# RadioRX.net
KiCad netlist of a schematic drawn in EAGLE
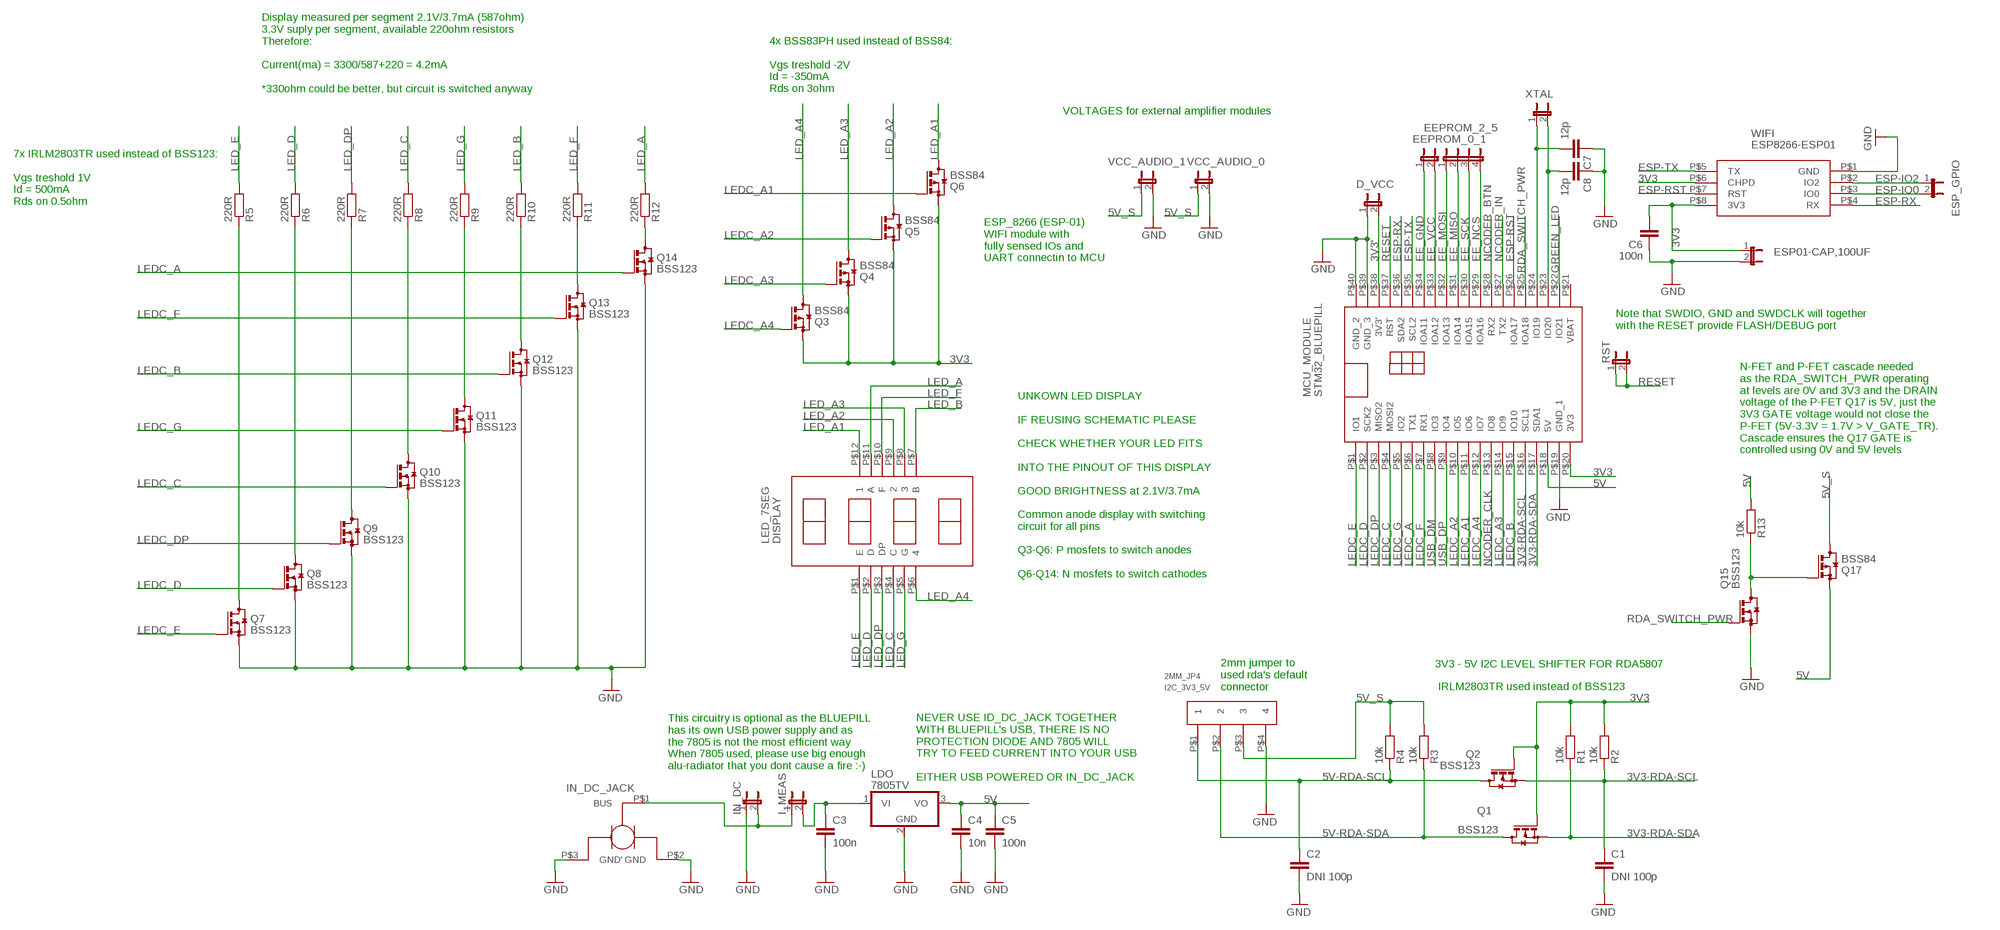
[diagram p0: schematic, sheet 1]

(export (version "E")
  (design (tool "Eeschema 10.0.6"))
  (components
    (comp (ref "C1")
      (value "DNI 100p")
      (footprint "eagle-import:C0805")
      (libsource (lib "eagle-import") (part "C-EUC0805"))
    )
    (comp (ref "C2")
      (value "DNI 100p")
      (footprint "eagle-import:C0805")
      (libsource (lib "eagle-import") (part "C-EUC0805"))
    )
    (comp (ref "C3")
      (value "100n")
      (footprint "eagle-import:C0805")
      (libsource (lib "eagle-import") (part "C-EUC0805"))
    )
    (comp (ref "C4")
      (value "10n")
      (footprint "eagle-import:C0805")
      (libsource (lib "eagle-import") (part "C-EUC0805"))
    )
    (comp (ref "C5")
      (value "100n")
      (footprint "eagle-import:C0805")
      (libsource (lib "eagle-import") (part "C-EUC0805"))
    )
    (comp (ref "C6")
      (value "100n")
      (footprint "eagle-import:C0805")
      (libsource (lib "eagle-import") (part "C-EUC0805"))
    )
    (comp (ref "C7")
      (value "12p")
      (footprint "eagle-import:C0603")
      (libsource (lib "eagle-import") (part "C-EUC0603"))
    )
    (comp (ref "C8")
      (value "12p")
      (footprint "eagle-import:C0603")
      (libsource (lib "eagle-import") (part "C-EUC0603"))
    )
    (comp (ref "DISPLAY")
      (value "LED_7SEG")
      (footprint "eagle-import:LED_7SEG")
      (libsource (lib "eagle-import") (part "LED_7SEG"))
    )
    (comp (ref "D_VCC")
      (value "JP1E")
      (footprint "eagle-import:JP1")
      (libsource (lib "eagle-import") (part "JP1E"))
    )
    (comp (ref "EEPROM_0_1")
      (value "JP1E")
      (footprint "eagle-import:JP1")
      (libsource (lib "eagle-import") (part "JP1E"))
    )
    (comp (ref "EEPROM_2_5")
      (value "JP4E")
      (footprint "eagle-import:JP4")
      (libsource (lib "eagle-import") (part "JP4E"))
    )
    (comp (ref "ESP01-CAP,100UF")
      (value "JP1E")
      (footprint "eagle-import:JP1")
      (libsource (lib "eagle-import") (part "JP1E"))
    )
    (comp (ref "ESP_GPIO")
      (value "JP1E")
      (footprint "eagle-import:JP1")
      (libsource (lib "eagle-import") (part "JP1E"))
    )
    (comp (ref "I2C_3V3_5V")
      (value "2MM_JP4")
      (footprint "eagle-import:2MM_JP4")
      (libsource (lib "eagle-import") (part "2MM_JP4"))
    )
    (comp (ref "IN_DC")
      (value "JP1E")
      (footprint "eagle-import:JP1")
      (libsource (lib "eagle-import") (part "JP1E"))
    )
    (comp (ref "IN_DC_JACK")
      (value "DC_CONN")
      (footprint "eagle-import:DC_CONN")
      (libsource (lib "eagle-import") (part "DC_CONN"))
    )
    (comp (ref "I_MEAS")
      (value "JP1E")
      (footprint "eagle-import:JP1")
      (libsource (lib "eagle-import") (part "JP1E"))
    )
    (comp (ref "LDO")
      (value "7805TV")
      (footprint "eagle-import:TO220V")
      (libsource (lib "eagle-import") (part "78TV05"))
    )
    (comp (ref "MCU_MODULE")
      (value "STM32_BLUEPILL")
      (footprint "eagle-import:STM32_BLUEPILL")
      (libsource (lib "eagle-import") (part "STM32_BLUEPILL"))
    )
    (comp (ref "Q1")
      (value "BSS123")
      (footprint "eagle-import:SOT23")
      (libsource (lib "eagle-import") (part "BSS123"))
    )
    (comp (ref "Q2")
      (value "BSS123")
      (footprint "eagle-import:SOT23")
      (libsource (lib "eagle-import") (part "BSS123"))
    )
    (comp (ref "Q3")
      (value "BSS84")
      (footprint "eagle-import:SOT23")
      (libsource (lib "eagle-import") (part "BSS84"))
    )
    (comp (ref "Q4")
      (value "BSS84")
      (footprint "eagle-import:SOT23")
      (libsource (lib "eagle-import") (part "BSS84"))
    )
    (comp (ref "Q5")
      (value "BSS84")
      (footprint "eagle-import:SOT23")
      (libsource (lib "eagle-import") (part "BSS84"))
    )
    (comp (ref "Q6")
      (value "BSS84")
      (footprint "eagle-import:SOT23")
      (libsource (lib "eagle-import") (part "BSS84"))
    )
    (comp (ref "Q7")
      (value "BSS123")
      (footprint "eagle-import:SOT23")
      (libsource (lib "eagle-import") (part "BSS123"))
    )
    (comp (ref "Q8")
      (value "BSS123")
      (footprint "eagle-import:SOT23")
      (libsource (lib "eagle-import") (part "BSS123"))
    )
    (comp (ref "Q9")
      (value "BSS123")
      (footprint "eagle-import:SOT23")
      (libsource (lib "eagle-import") (part "BSS123"))
    )
    (comp (ref "Q10")
      (value "BSS123")
      (footprint "eagle-import:SOT23")
      (libsource (lib "eagle-import") (part "BSS123"))
    )
    (comp (ref "Q11")
      (value "BSS123")
      (footprint "eagle-import:SOT23")
      (libsource (lib "eagle-import") (part "BSS123"))
    )
    (comp (ref "Q12")
      (value "BSS123")
      (footprint "eagle-import:SOT23")
      (libsource (lib "eagle-import") (part "BSS123"))
    )
    (comp (ref "Q13")
      (value "BSS123")
      (footprint "eagle-import:SOT23")
      (libsource (lib "eagle-import") (part "BSS123"))
    )
    (comp (ref "Q14")
      (value "BSS123")
      (footprint "eagle-import:SOT23")
      (libsource (lib "eagle-import") (part "BSS123"))
    )
    (comp (ref "Q15")
      (value "BSS123")
      (footprint "eagle-import:SOT23")
      (libsource (lib "eagle-import") (part "BSS123"))
    )
    (comp (ref "Q17")
      (value "BSS84")
      (footprint "eagle-import:SOT23")
      (libsource (lib "eagle-import") (part "BSS84"))
    )
    (comp (ref "R1")
      (value "10k")
      (footprint "eagle-import:R0805")
      (libsource (lib "eagle-import") (part "R-EU_R0805"))
    )
    (comp (ref "R2")
      (value "10k")
      (footprint "eagle-import:R0805")
      (libsource (lib "eagle-import") (part "R-EU_R0805"))
    )
    (comp (ref "R3")
      (value "10k")
      (footprint "eagle-import:R0805")
      (libsource (lib "eagle-import") (part "R-EU_R0805"))
    )
    (comp (ref "R4")
      (value "10k")
      (footprint "eagle-import:R0805")
      (libsource (lib "eagle-import") (part "R-EU_R0805"))
    )
    (comp (ref "R5")
      (value "220R")
      (footprint "eagle-import:R0805")
      (libsource (lib "eagle-import") (part "R-EU_R0805"))
    )
    (comp (ref "R6")
      (value "220R")
      (footprint "eagle-import:R0805")
      (libsource (lib "eagle-import") (part "R-EU_R0805"))
    )
    (comp (ref "R7")
      (value "220R")
      (footprint "eagle-import:R0805")
      (libsource (lib "eagle-import") (part "R-EU_R0805"))
    )
    (comp (ref "R8")
      (value "220R")
      (footprint "eagle-import:R0805")
      (libsource (lib "eagle-import") (part "R-EU_R0805"))
    )
    (comp (ref "R9")
      (value "220R")
      (footprint "eagle-import:R0805")
      (libsource (lib "eagle-import") (part "R-EU_R0805"))
    )
    (comp (ref "R10")
      (value "220R")
      (footprint "eagle-import:R0805")
      (libsource (lib "eagle-import") (part "R-EU_R0805"))
    )
    (comp (ref "R11")
      (value "220R")
      (footprint "eagle-import:R0805")
      (libsource (lib "eagle-import") (part "R-EU_R0805"))
    )
    (comp (ref "R12")
      (value "220R")
      (footprint "eagle-import:R0805")
      (libsource (lib "eagle-import") (part "R-EU_R0805"))
    )
    (comp (ref "R13")
      (value "10k")
      (footprint "eagle-import:R0805")
      (libsource (lib "eagle-import") (part "R-EU_R0805"))
    )
    (comp (ref "RST")
      (value "JP1E")
      (footprint "eagle-import:JP1")
      (libsource (lib "eagle-import") (part "JP1E"))
    )
    (comp (ref "VCC_AUDIO_0")
      (value "JP1E")
      (footprint "eagle-import:JP1")
      (libsource (lib "eagle-import") (part "JP1E"))
    )
    (comp (ref "VCC_AUDIO_1")
      (value "JP1E")
      (footprint "eagle-import:JP1")
      (libsource (lib "eagle-import") (part "JP1E"))
    )
    (comp (ref "WIFI")
      (value "ESP8266-ESP01")
      (footprint "eagle-import:ESP8266-ESP01")
      (libsource (lib "eagle-import") (part "ESP8266-ESP01"))
    )
    (comp (ref "XTAL")
      (value "JP1E")
      (footprint "eagle-import:JP1")
      (libsource (lib "eagle-import") (part "JP1E"))
    )
  )
  (nets
    (net (code "1") (name "/3V3") (class "Default")
      (node (ref "C6") (pin "2") (pinfunction "2_2") (pintype "passive"))
      (node (ref "ESP01-CAP,100UF") (pin "1") (pinfunction "1_1") (pintype "passive"))
      (node (ref "MCU_MODULE") (pin "P$20") (pinfunction "3V3_P$20") (pintype "bidirectional"))
      (node (ref "Q1") (pin "1") (pinfunction "G_1") (pintype "passive"))
      (node (ref "Q2") (pin "1") (pinfunction "G_1") (pintype "passive"))
      (node (ref "Q3") (pin "2") (pinfunction "S_2") (pintype "passive"))
      (node (ref "Q4") (pin "2") (pinfunction "S_2") (pintype "passive"))
      (node (ref "Q5") (pin "2") (pinfunction "S_2") (pintype "passive"))
      (node (ref "Q6") (pin "2") (pinfunction "S_2") (pintype "passive"))
      (node (ref "R1") (pin "2") (pinfunction "2_2") (pintype "passive"))
      (node (ref "R2") (pin "2") (pinfunction "2_2") (pintype "passive"))
      (node (ref "WIFI") (pin "P$6") (pinfunction "CHPD_P$6") (pintype "bidirectional"))
      (node (ref "WIFI") (pin "P$8") (pinfunction "3V3_P$8") (pintype "bidirectional"))
    )
    (net (code "2") (name "/3V3'") (class "Default")
      (node (ref "D_VCC") (pin "2") (pinfunction "2_2") (pintype "passive"))
      (node (ref "MCU_MODULE") (pin "P$38") (pinfunction "3V3'_P$38") (pintype "bidirectional"))
    )
    (net (code "3") (name "/3V3-RDA-SCL") (class "Default")
      (node (ref "C1") (pin "1") (pinfunction "1_1") (pintype "passive"))
      (node (ref "MCU_MODULE") (pin "P$16") (pinfunction "SCL1_P$16") (pintype "bidirectional"))
      (node (ref "Q2") (pin "2") (pinfunction "S_2") (pintype "passive"))
      (node (ref "R2") (pin "1") (pinfunction "1_1") (pintype "passive"))
    )
    (net (code "4") (name "/3V3-RDA-SDA") (class "Default")
      (node (ref "MCU_MODULE") (pin "P$17") (pinfunction "SDA1_P$17") (pintype "bidirectional"))
      (node (ref "Q1") (pin "2") (pinfunction "S_2") (pintype "passive"))
      (node (ref "R1") (pin "1") (pinfunction "1_1") (pintype "passive"))
    )
    (net (code "5") (name "/5V") (class "Default")
      (node (ref "C4") (pin "1") (pinfunction "1_1") (pintype "passive"))
      (node (ref "C5") (pin "1") (pinfunction "1_1") (pintype "passive"))
      (node (ref "LDO") (pin "3") (pinfunction "VO_3") (pintype "passive"))
      (node (ref "MCU_MODULE") (pin "P$18") (pinfunction "5V_P$18") (pintype "bidirectional"))
      (node (ref "Q17") (pin "2") (pinfunction "S_2") (pintype "passive"))
      (node (ref "R13") (pin "2") (pinfunction "2_2") (pintype "passive"))
    )
    (net (code "6") (name "/5V-RDA-SCL") (class "Default")
      (node (ref "C2") (pin "1") (pinfunction "1_1") (pintype "passive"))
      (node (ref "I2C_3V3_5V") (pin "P$1") (pinfunction "1_P$1") (pintype "bidirectional"))
      (node (ref "Q2") (pin "3") (pinfunction "D_3") (pintype "passive"))
      (node (ref "R4") (pin "1") (pinfunction "1_1") (pintype "passive"))
    )
    (net (code "7") (name "/5V-RDA-SDA") (class "Default")
      (node (ref "I2C_3V3_5V") (pin "P$2") (pinfunction "2_P$2") (pintype "bidirectional"))
      (node (ref "Q1") (pin "3") (pinfunction "D_3") (pintype "passive"))
      (node (ref "R3") (pin "1") (pinfunction "1_1") (pintype "passive"))
    )
    (net (code "8") (name "/5V_S") (class "Default")
      (node (ref "I2C_3V3_5V") (pin "P$3") (pinfunction "3_P$3") (pintype "bidirectional"))
      (node (ref "Q17") (pin "3") (pinfunction "D_3") (pintype "passive"))
      (node (ref "R3") (pin "2") (pinfunction "2_2") (pintype "passive"))
      (node (ref "R4") (pin "2") (pinfunction "2_2") (pintype "passive"))
      (node (ref "VCC_AUDIO_0") (pin "1") (pinfunction "1_1") (pintype "passive"))
      (node (ref "VCC_AUDIO_1") (pin "1") (pinfunction "1_1") (pintype "passive"))
    )
    (net (code "9") (name "/EE_GND") (class "Default")
      (node (ref "EEPROM_0_1") (pin "1") (pinfunction "1_1") (pintype "passive"))
      (node (ref "MCU_MODULE") (pin "P$34") (pinfunction "IOA11_P$34") (pintype "bidirectional"))
    )
    (net (code "10") (name "/EE_MISO") (class "Default")
      (node (ref "EEPROM_2_5") (pin "2") (pinfunction "2_2") (pintype "passive"))
      (node (ref "MCU_MODULE") (pin "P$31") (pinfunction "IOA14_P$31") (pintype "bidirectional"))
    )
    (net (code "11") (name "/EE_MOSI") (class "Default")
      (node (ref "EEPROM_2_5") (pin "1") (pinfunction "1_1") (pintype "passive"))
      (node (ref "MCU_MODULE") (pin "P$32") (pinfunction "IOA13_P$32") (pintype "bidirectional"))
    )
    (net (code "12") (name "/EE_NCS") (class "Default")
      (node (ref "EEPROM_2_5") (pin "4") (pinfunction "4_4") (pintype "passive"))
      (node (ref "MCU_MODULE") (pin "P$29") (pinfunction "IOA16_P$29") (pintype "bidirectional"))
    )
    (net (code "13") (name "/EE_SCK") (class "Default")
      (node (ref "EEPROM_2_5") (pin "3") (pinfunction "3_3") (pintype "passive"))
      (node (ref "MCU_MODULE") (pin "P$30") (pinfunction "IOA15_P$30") (pintype "bidirectional"))
    )
    (net (code "14") (name "/EE_VCC") (class "Default")
      (node (ref "EEPROM_0_1") (pin "2") (pinfunction "2_2") (pintype "passive"))
      (node (ref "MCU_MODULE") (pin "P$33") (pinfunction "IOA12_P$33") (pintype "bidirectional"))
    )
    (net (code "15") (name "/ESP-IO0") (class "Default")
      (node (ref "ESP_GPIO") (pin "2") (pinfunction "2_2") (pintype "passive"))
      (node (ref "WIFI") (pin "P$3") (pinfunction "IO0_P$3") (pintype "bidirectional"))
    )
    (net (code "16") (name "/ESP-IO2") (class "Default")
      (node (ref "ESP_GPIO") (pin "1") (pinfunction "1_1") (pintype "passive"))
      (node (ref "WIFI") (pin "P$2") (pinfunction "IO2_P$2") (pintype "bidirectional"))
    )
    (net (code "17") (name "/ESP-RST") (class "Default")
      (node (ref "MCU_MODULE") (pin "P$26") (pinfunction "IOA17_P$26") (pintype "bidirectional"))
      (node (ref "WIFI") (pin "P$7") (pinfunction "RST_P$7") (pintype "bidirectional"))
    )
    (net (code "18") (name "/ESP-RX") (class "Default")
      (node (ref "MCU_MODULE") (pin "P$36") (pinfunction "SDA2_P$36") (pintype "bidirectional"))
      (node (ref "WIFI") (pin "P$4") (pinfunction "RX_P$4") (pintype "bidirectional"))
    )
    (net (code "19") (name "/ESP-TX") (class "Default")
      (node (ref "MCU_MODULE") (pin "P$35") (pinfunction "SCL2_P$35") (pintype "bidirectional"))
      (node (ref "WIFI") (pin "P$5") (pinfunction "TX_P$5") (pintype "bidirectional"))
    )
    (net (code "20") (name "/GREEN_LED") (class "Default")
      (node (ref "MCU_MODULE") (pin "P$22") (pinfunction "IO21_P$22") (pintype "bidirectional"))
    )
    (net (code "21") (name "/LEDC_A") (class "Default")
      (node (ref "MCU_MODULE") (pin "P$6") (pinfunction "TX1_P$6") (pintype "bidirectional"))
      (node (ref "Q14") (pin "1") (pinfunction "G_1") (pintype "passive"))
    )
    (net (code "22") (name "/LEDC_A1") (class "Default")
      (node (ref "MCU_MODULE") (pin "P$11") (pinfunction "IO6_P$11") (pintype "bidirectional"))
      (node (ref "Q6") (pin "1") (pinfunction "G_1") (pintype "passive"))
    )
    (net (code "23") (name "/LEDC_A2") (class "Default")
      (node (ref "MCU_MODULE") (pin "P$10") (pinfunction "IO5_P$10") (pintype "bidirectional"))
      (node (ref "Q5") (pin "1") (pinfunction "G_1") (pintype "passive"))
    )
    (net (code "24") (name "/LEDC_A3") (class "Default")
      (node (ref "MCU_MODULE") (pin "P$14") (pinfunction "IO9_P$14") (pintype "bidirectional"))
      (node (ref "Q4") (pin "1") (pinfunction "G_1") (pintype "passive"))
    )
    (net (code "25") (name "/LEDC_A4") (class "Default")
      (node (ref "MCU_MODULE") (pin "P$12") (pinfunction "IO7_P$12") (pintype "bidirectional"))
      (node (ref "Q3") (pin "1") (pinfunction "G_1") (pintype "passive"))
    )
    (net (code "26") (name "/LEDC_B") (class "Default")
      (node (ref "MCU_MODULE") (pin "P$15") (pinfunction "IO10_P$15") (pintype "bidirectional"))
      (node (ref "Q12") (pin "1") (pinfunction "G_1") (pintype "passive"))
    )
    (net (code "27") (name "/LEDC_C") (class "Default")
      (node (ref "MCU_MODULE") (pin "P$4") (pinfunction "MOSI2_P$4") (pintype "bidirectional"))
      (node (ref "Q10") (pin "1") (pinfunction "G_1") (pintype "passive"))
    )
    (net (code "28") (name "/LEDC_D") (class "Default")
      (node (ref "MCU_MODULE") (pin "P$2") (pinfunction "SCK2_P$2") (pintype "bidirectional"))
      (node (ref "Q8") (pin "1") (pinfunction "G_1") (pintype "passive"))
    )
    (net (code "29") (name "/LEDC_DP") (class "Default")
      (node (ref "MCU_MODULE") (pin "P$3") (pinfunction "MISO2_P$3") (pintype "bidirectional"))
      (node (ref "Q9") (pin "1") (pinfunction "G_1") (pintype "passive"))
    )
    (net (code "30") (name "/LEDC_E") (class "Default")
      (node (ref "MCU_MODULE") (pin "P$1") (pinfunction "IO1_P$1") (pintype "bidirectional"))
      (node (ref "Q7") (pin "1") (pinfunction "G_1") (pintype "passive"))
    )
    (net (code "31") (name "/LEDC_F") (class "Default")
      (node (ref "MCU_MODULE") (pin "P$7") (pinfunction "RX1_P$7") (pintype "bidirectional"))
      (node (ref "Q13") (pin "1") (pinfunction "G_1") (pintype "passive"))
    )
    (net (code "32") (name "/LEDC_G") (class "Default")
      (node (ref "MCU_MODULE") (pin "P$5") (pinfunction "IO2_P$5") (pintype "bidirectional"))
      (node (ref "Q11") (pin "1") (pinfunction "G_1") (pintype "passive"))
    )
    (net (code "33") (name "/LED_A") (class "Default")
      (node (ref "DISPLAY") (pin "P$11") (pinfunction "A_P$11") (pintype "bidirectional"))
      (node (ref "R12") (pin "2") (pinfunction "2_2") (pintype "passive"))
    )
    (net (code "34") (name "/LED_A1") (class "Default")
      (node (ref "DISPLAY") (pin "P$12") (pinfunction "1_P$12") (pintype "bidirectional"))
      (node (ref "Q6") (pin "3") (pinfunction "D_3") (pintype "passive"))
    )
    (net (code "35") (name "/LED_A2") (class "Default")
      (node (ref "DISPLAY") (pin "P$9") (pinfunction "2_P$9") (pintype "bidirectional"))
      (node (ref "Q5") (pin "3") (pinfunction "D_3") (pintype "passive"))
    )
    (net (code "36") (name "/LED_A3") (class "Default")
      (node (ref "DISPLAY") (pin "P$8") (pinfunction "3_P$8") (pintype "bidirectional"))
      (node (ref "Q4") (pin "3") (pinfunction "D_3") (pintype "passive"))
    )
    (net (code "37") (name "/LED_A4") (class "Default")
      (node (ref "DISPLAY") (pin "P$6") (pinfunction "4_P$6") (pintype "bidirectional"))
      (node (ref "Q3") (pin "3") (pinfunction "D_3") (pintype "passive"))
    )
    (net (code "38") (name "/LED_B") (class "Default")
      (node (ref "DISPLAY") (pin "P$7") (pinfunction "B_P$7") (pintype "bidirectional"))
      (node (ref "R10") (pin "2") (pinfunction "2_2") (pintype "passive"))
    )
    (net (code "39") (name "/LED_C") (class "Default")
      (node (ref "DISPLAY") (pin "P$4") (pinfunction "C_P$4") (pintype "bidirectional"))
      (node (ref "R8") (pin "2") (pinfunction "2_2") (pintype "passive"))
    )
    (net (code "40") (name "/LED_D") (class "Default")
      (node (ref "DISPLAY") (pin "P$2") (pinfunction "D_P$2") (pintype "bidirectional"))
      (node (ref "R6") (pin "2") (pinfunction "2_2") (pintype "passive"))
    )
    (net (code "41") (name "/LED_DP") (class "Default")
      (node (ref "DISPLAY") (pin "P$3") (pinfunction "DP_P$3") (pintype "bidirectional"))
      (node (ref "R7") (pin "2") (pinfunction "2_2") (pintype "passive"))
    )
    (net (code "42") (name "/LED_E") (class "Default")
      (node (ref "DISPLAY") (pin "P$1") (pinfunction "E_P$1") (pintype "bidirectional"))
      (node (ref "R5") (pin "2") (pinfunction "2_2") (pintype "passive"))
    )
    (net (code "43") (name "/LED_F") (class "Default")
      (node (ref "DISPLAY") (pin "P$10") (pinfunction "F_P$10") (pintype "bidirectional"))
      (node (ref "R11") (pin "2") (pinfunction "2_2") (pintype "passive"))
    )
    (net (code "44") (name "/LED_G") (class "Default")
      (node (ref "DISPLAY") (pin "P$5") (pinfunction "G_P$5") (pintype "bidirectional"))
      (node (ref "R9") (pin "2") (pinfunction "2_2") (pintype "passive"))
    )
    (net (code "45") (name "/NCODER_BTN") (class "Default")
      (node (ref "MCU_MODULE") (pin "P$28") (pinfunction "RX2_P$28") (pintype "bidirectional"))
    )
    (net (code "46") (name "/NCODER_CLK") (class "Default")
      (node (ref "MCU_MODULE") (pin "P$13") (pinfunction "IO8_P$13") (pintype "bidirectional"))
    )
    (net (code "47") (name "/NCODER_IN") (class "Default")
      (node (ref "MCU_MODULE") (pin "P$27") (pinfunction "TX2_P$27") (pintype "bidirectional"))
    )
    (net (code "48") (name "/RDA_SWITCH_PWR") (class "Default")
      (node (ref "MCU_MODULE") (pin "P$25") (pinfunction "IOA18_P$25") (pintype "bidirectional"))
      (node (ref "Q15") (pin "1") (pinfunction "G_1") (pintype "passive"))
    )
    (net (code "49") (name "/RESET") (class "Default")
      (node (ref "MCU_MODULE") (pin "P$37") (pinfunction "RST_P$37") (pintype "bidirectional"))
      (node (ref "RST") (pin "1") (pinfunction "1_1") (pintype "passive"))
      (node (ref "RST") (pin "2") (pinfunction "2_2") (pintype "passive"))
    )
    (net (code "50") (name "/USB_DM") (class "Default")
      (node (ref "MCU_MODULE") (pin "P$8") (pinfunction "IO3_P$8") (pintype "bidirectional"))
    )
    (net (code "51") (name "/USB_DP") (class "Default")
      (node (ref "MCU_MODULE") (pin "P$9") (pinfunction "IO4_P$9") (pintype "bidirectional"))
    )
    (net (code "52") (name "GND") (class "Default")
      (node (ref "C1") (pin "2") (pinfunction "2_2") (pintype "passive"))
      (node (ref "C2") (pin "2") (pinfunction "2_2") (pintype "passive"))
      (node (ref "C3") (pin "2") (pinfunction "2_2") (pintype "passive"))
      (node (ref "C4") (pin "2") (pinfunction "2_2") (pintype "passive"))
      (node (ref "C5") (pin "2") (pinfunction "2_2") (pintype "passive"))
      (node (ref "C6") (pin "1") (pinfunction "1_1") (pintype "passive"))
      (node (ref "C7") (pin "1") (pinfunction "1_1") (pintype "passive"))
      (node (ref "C8") (pin "1") (pinfunction "1_1") (pintype "passive"))
      (node (ref "D_VCC") (pin "1") (pinfunction "1_1") (pintype "passive"))
      (node (ref "ESP01-CAP,100UF") (pin "2") (pinfunction "2_2") (pintype "passive"))
      (node (ref "I2C_3V3_5V") (pin "P$4") (pinfunction "4_P$4") (pintype "bidirectional"))
      (node (ref "IN_DC") (pin "1") (pinfunction "1_1") (pintype "passive"))
      (node (ref "IN_DC_JACK") (pin "P$2") (pinfunction "GND_P$2") (pintype "bidirectional"))
      (node (ref "IN_DC_JACK") (pin "P$3") (pinfunction "GND'_P$3") (pintype "bidirectional"))
      (node (ref "LDO") (pin "2") (pinfunction "GND_2") (pintype "passive"))
      (node (ref "MCU_MODULE") (pin "P$19") (pinfunction "GND_1_P$19") (pintype "bidirectional"))
      (node (ref "MCU_MODULE") (pin "P$39") (pinfunction "GND_3_P$39") (pintype "bidirectional"))
      (node (ref "MCU_MODULE") (pin "P$40") (pinfunction "GND_2_P$40") (pintype "bidirectional"))
      (node (ref "Q10") (pin "2") (pinfunction "S_2") (pintype "passive"))
      (node (ref "Q11") (pin "2") (pinfunction "S_2") (pintype "passive"))
      (node (ref "Q12") (pin "2") (pinfunction "S_2") (pintype "passive"))
      (node (ref "Q13") (pin "2") (pinfunction "S_2") (pintype "passive"))
      (node (ref "Q14") (pin "2") (pinfunction "S_2") (pintype "passive"))
      (node (ref "Q15") (pin "2") (pinfunction "S_2") (pintype "passive"))
      (node (ref "Q7") (pin "2") (pinfunction "S_2") (pintype "passive"))
      (node (ref "Q8") (pin "2") (pinfunction "S_2") (pintype "passive"))
      (node (ref "Q9") (pin "2") (pinfunction "S_2") (pintype "passive"))
      (node (ref "VCC_AUDIO_0") (pin "2") (pinfunction "2_2") (pintype "passive"))
      (node (ref "VCC_AUDIO_1") (pin "2") (pinfunction "2_2") (pintype "passive"))
      (node (ref "WIFI") (pin "P$1") (pinfunction "GND_P$1") (pintype "bidirectional"))
    )
    (net (code "53") (name "Net-(IN_DC_JACK-BUS)") (class "Default")
      (node (ref "IN_DC") (pin "2") (pinfunction "2_2") (pintype "passive"))
      (node (ref "IN_DC_JACK") (pin "P$1") (pinfunction "BUS_P$1") (pintype "bidirectional"))
      (node (ref "I_MEAS") (pin "1") (pinfunction "1_1") (pintype "passive"))
    )
    (net (code "54") (name "Net-(LDO-VI)") (class "Default")
      (node (ref "C3") (pin "1") (pinfunction "1_1") (pintype "passive"))
      (node (ref "I_MEAS") (pin "2") (pinfunction "2_2") (pintype "passive"))
      (node (ref "LDO") (pin "1") (pinfunction "VI_1") (pintype "input"))
    )
    (net (code "55") (name "Net-(MCU_MODULE-IO19)") (class "Default")
      (node (ref "C7") (pin "2") (pinfunction "2_2") (pintype "passive"))
      (node (ref "MCU_MODULE") (pin "P$24") (pinfunction "IO19_P$24") (pintype "bidirectional"))
      (node (ref "XTAL") (pin "1") (pinfunction "1_1") (pintype "passive"))
    )
    (net (code "56") (name "Net-(MCU_MODULE-IO20)") (class "Default")
      (node (ref "C8") (pin "2") (pinfunction "2_2") (pintype "passive"))
      (node (ref "MCU_MODULE") (pin "P$23") (pinfunction "IO20_P$23") (pintype "bidirectional"))
      (node (ref "XTAL") (pin "2") (pinfunction "2_2") (pintype "passive"))
    )
    (net (code "57") (name "Net-(Q7-D)") (class "Default")
      (node (ref "Q7") (pin "3") (pinfunction "D_3") (pintype "passive"))
      (node (ref "R5") (pin "1") (pinfunction "1_1") (pintype "passive"))
    )
    (net (code "58") (name "Net-(Q8-D)") (class "Default")
      (node (ref "Q8") (pin "3") (pinfunction "D_3") (pintype "passive"))
      (node (ref "R6") (pin "1") (pinfunction "1_1") (pintype "passive"))
    )
    (net (code "59") (name "Net-(Q9-D)") (class "Default")
      (node (ref "Q9") (pin "3") (pinfunction "D_3") (pintype "passive"))
      (node (ref "R7") (pin "1") (pinfunction "1_1") (pintype "passive"))
    )
    (net (code "60") (name "Net-(Q10-D)") (class "Default")
      (node (ref "Q10") (pin "3") (pinfunction "D_3") (pintype "passive"))
      (node (ref "R8") (pin "1") (pinfunction "1_1") (pintype "passive"))
    )
    (net (code "61") (name "Net-(Q11-D)") (class "Default")
      (node (ref "Q11") (pin "3") (pinfunction "D_3") (pintype "passive"))
      (node (ref "R9") (pin "1") (pinfunction "1_1") (pintype "passive"))
    )
    (net (code "62") (name "Net-(Q12-D)") (class "Default")
      (node (ref "Q12") (pin "3") (pinfunction "D_3") (pintype "passive"))
      (node (ref "R10") (pin "1") (pinfunction "1_1") (pintype "passive"))
    )
    (net (code "63") (name "Net-(Q13-D)") (class "Default")
      (node (ref "Q13") (pin "3") (pinfunction "D_3") (pintype "passive"))
      (node (ref "R11") (pin "1") (pinfunction "1_1") (pintype "passive"))
    )
    (net (code "64") (name "Net-(Q14-D)") (class "Default")
      (node (ref "Q14") (pin "3") (pinfunction "D_3") (pintype "passive"))
      (node (ref "R12") (pin "1") (pinfunction "1_1") (pintype "passive"))
    )
    (net (code "65") (name "Net-(Q15-D)") (class "Default")
      (node (ref "Q15") (pin "3") (pinfunction "D_3") (pintype "passive"))
      (node (ref "Q17") (pin "1") (pinfunction "G_1") (pintype "passive"))
      (node (ref "R13") (pin "1") (pinfunction "1_1") (pintype "passive"))
    )
    (net (code "66") (name "unconnected-(MCU_MODULE-VBAT-PadP$21)") (class "Default")
      (node (ref "MCU_MODULE") (pin "P$21") (pinfunction "VBAT_P$21") (pintype "bidirectional"))
    )
  )
)
